# EC_meter_v2.net
KiCad netlist of a schematic drawn in Altium Designer
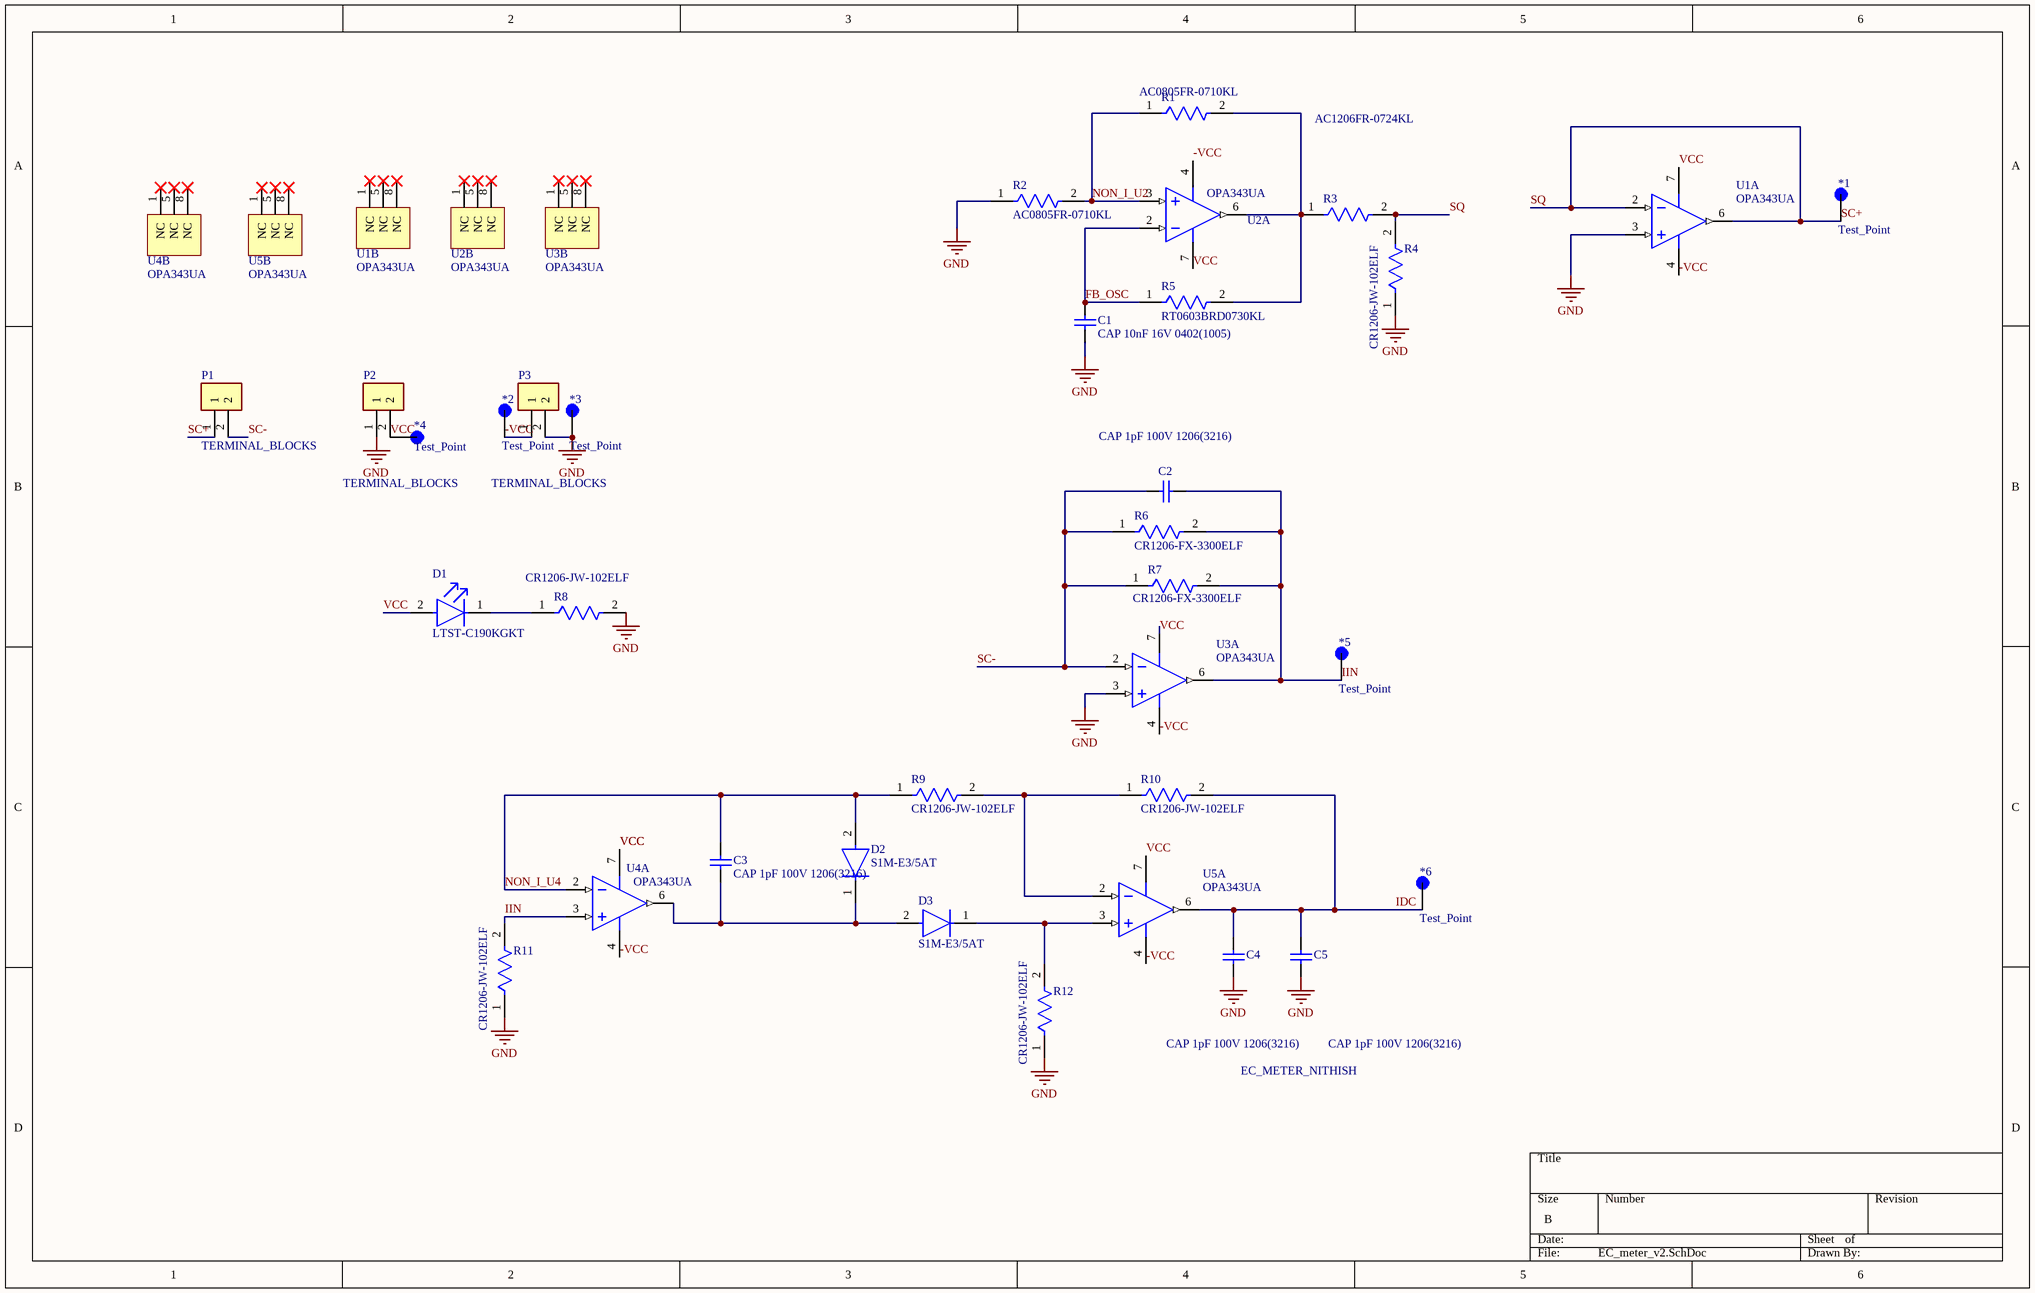
[diagram p0: EC_meter_v2.SchDoc]

(export (version "E")
  (design (tool "Eeschema 10.0.6"))
  (components
    (comp (ref "*1")
      (value "Test_Point")
      (footprint "Test_point")
      (libsource (lib "EC_meter_v2") (part "Test_Point"))
    )
    (comp (ref "*2")
      (value "Test_Point")
      (footprint "Test_point")
      (libsource (lib "EC_meter_v2") (part "Test_Point"))
    )
    (comp (ref "*3")
      (value "Test_Point")
      (footprint "Test_point")
      (libsource (lib "EC_meter_v2") (part "Test_Point"))
    )
    (comp (ref "*4")
      (value "Test_Point")
      (footprint "Test_point")
      (libsource (lib "EC_meter_v2") (part "Test_Point"))
    )
    (comp (ref "*5")
      (value "Test_Point")
      (footprint "Test_point")
      (libsource (lib "EC_meter_v2") (part "Test_Point"))
    )
    (comp (ref "*6")
      (value "Test_Point")
      (footprint "Test_point")
      (libsource (lib "EC_meter_v2") (part "Test_Point"))
    )
    (comp (ref "C1")
      (value "CAP 10nF 16V 0402(1005)")
      (footprint "CAPC0402(1005)60_M")
      (description "CAP 10nF 16V -20% to +80% 0402 (1005 Metric) Thickness 0.6mm SMD")
      (fields (field (name "TOLERANCE") "-20% to +80%"))
      (libsource (lib "Altium Content Vault") (part "CAP"))
    )
    (comp (ref "C2")
      (value "CAP 1pF 100V 1206(3216)")
      (footprint "CAPC1206(3216)170_N")
      (description "CAP 1pF 100V ±0.25pF 1206 (3216 Metric) Thickness 1.7mm SMD")
      (fields (field (name "TOLERANCE") "Â±0.25pF"))
      (libsource (lib "Altium Content Vault") (part "CAP"))
    )
    (comp (ref "C3")
      (value "CAP 1pF 100V 1206(3216)")
      (footprint "CAPC1206(3216)170_N")
      (description "CAP 1pF 100V ±0.25pF 1206 (3216 Metric) Thickness 1.7mm SMD")
      (fields (field (name "TOLERANCE") "Â±0.25pF"))
      (libsource (lib "Altium Content Vault") (part "CAP"))
    )
    (comp (ref "C4")
      (value "CAP 1pF 100V 1206(3216)")
      (footprint "CAPC1206(3216)170_N")
      (description "CAP 1pF 100V ±0.25pF 1206 (3216 Metric) Thickness 1.7mm SMD")
      (fields (field (name "TOLERANCE") "Â±0.25pF"))
      (libsource (lib "Altium Content Vault") (part "CAP"))
    )
    (comp (ref "C5")
      (value "CAP 1pF 100V 1206(3216)")
      (footprint "CAPC1206(3216)170_N")
      (description "CAP 1pF 100V ±0.25pF 1206 (3216 Metric) Thickness 1.7mm SMD")
      (fields (field (name "TOLERANCE") "Â±0.25pF"))
      (libsource (lib "Altium Content Vault") (part "CAP"))
    )
    (comp (ref "D1")
      (value "LTST-C190KGKT")
      (footprint "FP-LTST-C190KGKT-MFG")
      (description "LED GREEN CLEAR CHIP SMD")
      (libsource (lib "Altium Content Vault") (part "8706943c75ba83719d021d2fdc84c58"))
    )
    (comp (ref "D2")
      (value "S1M-E3/5AT")
      (footprint "FP-95400-MFG")
      (description "DIODE GEN PURP 1KV 1A DO214AC")
      (fields
        (field (name "OCTOPART") "https://octopart.com/s1m-e3%2F5at-vishay-42334588")
        (field (name "MANUFACTURER") "Vishay")
      )
      (libsource (lib "Altium Content Vault") (part "d7152d700b627762746794eb795d46e"))
    )
    (comp (ref "D3")
      (value "S1M-E3/5AT")
      (footprint "FP-95400-MFG")
      (description "DIODE GEN PURP 1KV 1A DO214AC")
      (fields
        (field (name "OCTOPART") "https://octopart.com/s1m-e3%2F5at-vishay-42334588")
        (field (name "MANUFACTURER") "Vishay")
      )
      (libsource (lib "Altium Content Vault") (part "d7152d700b627762746794eb795d46e"))
    )
    (comp (ref "P1")
      (value "TERMINAL_BLOCKS")
      (footprint "PCBComponent_1 - duplicate")
      (libsource (lib "EC_meter") (part "TERMINAL_BLOCKS"))
    )
    (comp (ref "P2")
      (value "TERMINAL_BLOCKS")
      (footprint "PCBComponent_1 - duplicate")
      (libsource (lib "EC_meter") (part "TERMINAL_BLOCKS"))
    )
    (comp (ref "P3")
      (value "TERMINAL_BLOCKS")
      (footprint "PCBComponent_1 - duplicate")
      (libsource (lib "EC_meter") (part "TERMINAL_BLOCKS"))
    )
    (comp (ref "R1")
      (value "AC0805FR-0710KL")
      (footprint "FP-AC0805-MFG")
      (description "RES SMD 10K OHM 1% 1/8W 0805")
      (fields
        (field (name "OCTOPART") "https://octopart.com/ac0805fr-0710kl-yageo-21711112")
        (field (name "MANUFACTURER") "Yageo")
      )
      (libsource (lib "Altium Content Vault") (part "1029c3af85768c4190bb7ad29bc67b5"))
    )
    (comp (ref "R2")
      (value "AC0805FR-0710KL")
      (footprint "FP-AC0805-MFG")
      (description "RES SMD 10K OHM 1% 1/8W 0805")
      (fields
        (field (name "OCTOPART") "https://octopart.com/ac0805fr-0710kl-yageo-21711112")
        (field (name "MANUFACTURER") "Yageo")
      )
      (libsource (lib "Altium Content Vault") (part "1029c3af85768c4190bb7ad29bc67b5"))
    )
    (comp (ref "R3")
      (value "AC1206FR-0724KL")
      (footprint "FP-AC1206-MFG")
      (description "RES SMD 24K OHM 1% 1/4W 1206")
      (fields
        (field (name "MANUFACTURER") "Yageo")
        (field (name "OCTOPART") "https://octopart.com/ac1206fr-0724kl-yageo-30511081")
      )
      (libsource (lib "Altium Content Vault") (part "1029c3af85768c4190bb7ad29bc67b5"))
    )
    (comp (ref "R4")
      (value "CR1206-JW-102ELF")
      (footprint "FP-CR1206-IPC_C")
      (description "Thick Film Chip Resistors 1206 1kΩ 0.25W 5% 200ppm/°C")
      (fields (field (name "TOLERANCE") "5%"))
      (libsource (lib "Altium Content Vault") (part "1029c3af85768c4190bb7ad29bc67b5"))
    )
    (comp (ref "R5")
      (value "RT0603BRD0730KL")
      (footprint "FP-RT0603-0_55-MFG")
      (fields (field (name "TOLERANCE") "0.1%"))
      (libsource (lib "Altium Content Vault") (part "1029c3af85768c4190bb7ad29bc67b5"))
    )
    (comp (ref "R6")
      (value "CR1206-FX-3300ELF")
      (footprint "FP-CR1206-MFG")
      (description "Thick Film Chip Resistors 1206 330Ω 0.25W 1% 100ppm/°C")
      (fields (field (name "TOLERANCE") "1%"))
      (libsource (lib "Altium Content Vault") (part "1029c3af85768c4190bb7ad29bc67b5"))
    )
    (comp (ref "R7")
      (value "CR1206-FX-3300ELF")
      (footprint "FP-CR1206-MFG")
      (description "Thick Film Chip Resistors 1206 330Ω 0.25W 1% 100ppm/°C")
      (fields (field (name "TOLERANCE") "1%"))
      (libsource (lib "Altium Content Vault") (part "1029c3af85768c4190bb7ad29bc67b5"))
    )
    (comp (ref "R8")
      (value "CR1206-JW-102ELF")
      (footprint "FP-CR1206-IPC_C")
      (description "Thick Film Chip Resistors 1206 1kΩ 0.25W 5% 200ppm/°C")
      (fields (field (name "TOLERANCE") "5%"))
      (libsource (lib "Altium Content Vault") (part "1029c3af85768c4190bb7ad29bc67b5"))
    )
    (comp (ref "R9")
      (value "CR1206-JW-102ELF")
      (footprint "FP-CR1206-IPC_C")
      (description "Thick Film Chip Resistors 1206 1kΩ 0.25W 5% 200ppm/°C")
      (fields (field (name "TOLERANCE") "5%"))
      (libsource (lib "Altium Content Vault") (part "1029c3af85768c4190bb7ad29bc67b5"))
    )
    (comp (ref "R10")
      (value "CR1206-JW-102ELF")
      (footprint "FP-CR1206-IPC_C")
      (description "Thick Film Chip Resistors 1206 1kΩ 0.25W 5% 200ppm/°C")
      (fields (field (name "TOLERANCE") "5%"))
      (libsource (lib "Altium Content Vault") (part "1029c3af85768c4190bb7ad29bc67b5"))
    )
    (comp (ref "R11")
      (value "CR1206-JW-102ELF")
      (footprint "FP-CR1206-IPC_C")
      (description "Thick Film Chip Resistors 1206 1kΩ 0.25W 5% 200ppm/°C")
      (fields (field (name "TOLERANCE") "5%"))
      (libsource (lib "Altium Content Vault") (part "1029c3af85768c4190bb7ad29bc67b5"))
    )
    (comp (ref "R12")
      (value "CR1206-JW-102ELF")
      (footprint "FP-CR1206-IPC_C")
      (description "Thick Film Chip Resistors 1206 1kΩ 0.25W 5% 200ppm/°C")
      (fields (field (name "TOLERANCE") "5%"))
      (libsource (lib "Altium Content Vault") (part "1029c3af85768c4190bb7ad29bc67b5"))
    )
    (comp (ref "U1")
      (value "OPA343UA")
      (footprint "D0008A_M")
      (fields (field (name "MANUFACTURER") "Texas Instruments"))
      (libsource (lib "Altium Content Vault") (part "TI-OPA-8_1"))
    )
    (comp (ref "U2")
      (value "OPA343UA")
      (footprint "D0008A_M")
      (fields (field (name "MANUFACTURER") "Texas Instruments"))
      (libsource (lib "Altium Content Vault") (part "TI-OPA-8_1"))
    )
    (comp (ref "U3")
      (value "OPA343UA")
      (footprint "D0008A_M")
      (fields (field (name "MANUFACTURER") "Texas Instruments"))
      (libsource (lib "") (part "TI-OPA-8_1_1"))
    )
    (comp (ref "U4")
      (value "OPA343UA")
      (footprint "D0008A_M")
      (fields (field (name "MANUFACTURER") "Texas Instruments"))
      (libsource (lib "") (part "TI-OPA-8_1_1"))
    )
    (comp (ref "U5")
      (value "OPA343UA")
      (footprint "D0008A_M")
      (fields (field (name "MANUFACTURER") "Texas Instruments"))
      (libsource (lib "") (part "TI-OPA-8_1_1"))
    )
  )
  (nets
    (net (code "1") (name "/-VCC") (class "Default")
      (node (ref "*2") (pin "1") (pinfunction "TP_1") (pintype "passive"))
      (node (ref "P3") (pin "1") (pinfunction "1_1") (pintype "passive"))
      (node (ref "U1") (pin "4") (pinfunction "V-_4") (pintype "power_in"))
      (node (ref "U2") (pin "4") (pinfunction "V-_4") (pintype "power_in"))
      (node (ref "U3") (pin "4") (pinfunction "V-_4") (pintype "power_in"))
      (node (ref "U4") (pin "4") (pinfunction "V-_4") (pintype "power_in"))
      (node (ref "U5") (pin "4") (pinfunction "V-_4") (pintype "power_in"))
    )
    (net (code "2") (name "/FB_OSC") (class "Default")
      (node (ref "C1") (pin "2") (pinfunction "2_2") (pintype "passive"))
      (node (ref "R5") (pin "1") (pinfunction "1_1") (pintype "passive"))
      (node (ref "U2") (pin "2") (pinfunction "IN-_2") (pintype "input"))
    )
    (net (code "3") (name "/IDC") (class "Default")
      (node (ref "*6") (pin "1") (pinfunction "TP_1") (pintype "passive"))
      (node (ref "C4") (pin "2") (pinfunction "2_2") (pintype "passive"))
      (node (ref "C5") (pin "2") (pinfunction "2_2") (pintype "passive"))
      (node (ref "R10") (pin "2") (pinfunction "2_2") (pintype "passive"))
      (node (ref "U5") (pin "6") (pinfunction "OUT_6") (pintype "output"))
    )
    (net (code "4") (name "/IIN") (class "Default")
      (node (ref "*5") (pin "1") (pinfunction "TP_1") (pintype "passive"))
      (node (ref "C2") (pin "1") (pinfunction "1_1") (pintype "passive"))
      (node (ref "R11") (pin "2") (pinfunction "2_2") (pintype "passive"))
      (node (ref "R6") (pin "2") (pinfunction "2_2") (pintype "passive"))
      (node (ref "R7") (pin "2") (pinfunction "2_2") (pintype "passive"))
      (node (ref "U3") (pin "6") (pinfunction "OUT_6") (pintype "output"))
      (node (ref "U4") (pin "3") (pinfunction "IN+_3") (pintype "input"))
    )
    (net (code "5") (name "/NON_I_U2") (class "Default")
      (node (ref "R1") (pin "1") (pinfunction "1_1") (pintype "passive"))
      (node (ref "R2") (pin "2") (pinfunction "2_2") (pintype "passive"))
      (node (ref "U2") (pin "3") (pinfunction "IN+_3") (pintype "input"))
    )
    (net (code "6") (name "/NON_I_U4") (class "Default")
      (node (ref "C3") (pin "2") (pinfunction "2_2") (pintype "passive"))
      (node (ref "D2") (pin "2") (pinfunction "A_2") (pintype "passive"))
      (node (ref "R9") (pin "1") (pinfunction "1_1") (pintype "passive"))
      (node (ref "U4") (pin "2") (pinfunction "IN-_2") (pintype "input"))
    )
    (net (code "7") (name "/SC+") (class "Default")
      (node (ref "*1") (pin "1") (pinfunction "TP_1") (pintype "passive"))
      (node (ref "P1") (pin "1") (pinfunction "1_1") (pintype "passive"))
      (node (ref "R3") (pin "2") (pinfunction "2_2") (pintype "passive"))
      (node (ref "R4") (pin "2") (pinfunction "2_2") (pintype "passive"))
      (node (ref "U1") (pin "2") (pinfunction "IN-_2") (pintype "input"))
      (node (ref "U1") (pin "6") (pinfunction "OUT_6") (pintype "output"))
    )
    (net (code "8") (name "/SC-") (class "Default")
      (node (ref "C2") (pin "2") (pinfunction "2_2") (pintype "passive"))
      (node (ref "P1") (pin "2") (pinfunction "2_2") (pintype "passive"))
      (node (ref "R6") (pin "1") (pinfunction "1_1") (pintype "passive"))
      (node (ref "R7") (pin "1") (pinfunction "1_1") (pintype "passive"))
      (node (ref "U3") (pin "2") (pinfunction "IN-_2") (pintype "input"))
    )
    (net (code "9") (name "/VCC") (class "Default")
      (node (ref "*4") (pin "1") (pinfunction "TP_1") (pintype "passive"))
      (node (ref "D1") (pin "2") (pinfunction "A_2") (pintype "passive"))
      (node (ref "P2") (pin "2") (pinfunction "2_2") (pintype "passive"))
      (node (ref "U1") (pin "7") (pinfunction "V+_7") (pintype "power_in"))
      (node (ref "U2") (pin "7") (pinfunction "V+_7") (pintype "power_in"))
      (node (ref "U3") (pin "7") (pinfunction "V+_7") (pintype "power_in"))
      (node (ref "U4") (pin "7") (pinfunction "V+_7") (pintype "power_in"))
      (node (ref "U5") (pin "7") (pinfunction "V+_7") (pintype "power_in"))
    )
    (net (code "10") (name "GND") (class "Default")
      (node (ref "*3") (pin "1") (pinfunction "TP_1") (pintype "passive"))
      (node (ref "C1") (pin "1") (pinfunction "1_1") (pintype "passive"))
      (node (ref "C4") (pin "1") (pinfunction "1_1") (pintype "passive"))
      (node (ref "C5") (pin "1") (pinfunction "1_1") (pintype "passive"))
      (node (ref "P2") (pin "1") (pinfunction "1_1") (pintype "passive"))
      (node (ref "P3") (pin "2") (pinfunction "2_2") (pintype "passive"))
      (node (ref "R11") (pin "1") (pinfunction "1_1") (pintype "passive"))
      (node (ref "R12") (pin "1") (pinfunction "1_1") (pintype "passive"))
      (node (ref "R2") (pin "1") (pinfunction "1_1") (pintype "passive"))
      (node (ref "R4") (pin "1") (pinfunction "1_1") (pintype "passive"))
      (node (ref "R8") (pin "2") (pinfunction "2_2") (pintype "passive"))
      (node (ref "U1") (pin "3") (pinfunction "IN+_3") (pintype "input"))
      (node (ref "U3") (pin "3") (pinfunction "IN+_3") (pintype "input"))
    )
    (net (code "11") (name "Net-(D1-C)") (class "Default")
      (node (ref "D1") (pin "1") (pinfunction "C_1") (pintype "passive"))
      (node (ref "R8") (pin "1") (pinfunction "1_1") (pintype "passive"))
    )
    (net (code "12") (name "Net-(D2-C)") (class "Default")
      (node (ref "C3") (pin "1") (pinfunction "1_1") (pintype "passive"))
      (node (ref "D2") (pin "1") (pinfunction "C_1") (pintype "passive"))
      (node (ref "D3") (pin "2") (pinfunction "A_2") (pintype "passive"))
      (node (ref "U4") (pin "6") (pinfunction "OUT_6") (pintype "output"))
    )
    (net (code "13") (name "Net-(D3-C)") (class "Default")
      (node (ref "D3") (pin "1") (pinfunction "C_1") (pintype "passive"))
      (node (ref "R12") (pin "2") (pinfunction "2_2") (pintype "passive"))
      (node (ref "U5") (pin "3") (pinfunction "IN+_3") (pintype "input"))
    )
    (net (code "14") (name "Net-(U2A-OUT)") (class "Default")
      (node (ref "R1") (pin "2") (pinfunction "2_2") (pintype "passive"))
      (node (ref "R3") (pin "1") (pinfunction "1_1") (pintype "passive"))
      (node (ref "R5") (pin "2") (pinfunction "2_2") (pintype "passive"))
      (node (ref "U2") (pin "6") (pinfunction "OUT_6") (pintype "output"))
    )
    (net (code "15") (name "Net-(U5A-IN-)") (class "Default")
      (node (ref "R10") (pin "1") (pinfunction "1_1") (pintype "passive"))
      (node (ref "R9") (pin "2") (pinfunction "2_2") (pintype "passive"))
      (node (ref "U5") (pin "2") (pinfunction "IN-_2") (pintype "input"))
    )
    (net (code "16") (name "unconnected-(U1B-NC-Pad1)") (class "Default")
      (node (ref "U1") (pin "1") (pinfunction "NC_1") (pintype "passive+no_connect"))
    )
    (net (code "17") (name "unconnected-(U1B-NC-Pad5)") (class "Default")
      (node (ref "U1") (pin "5") (pinfunction "NC_5") (pintype "passive+no_connect"))
    )
    (net (code "18") (name "unconnected-(U1B-NC-Pad8)") (class "Default")
      (node (ref "U1") (pin "8") (pinfunction "NC_8") (pintype "passive+no_connect"))
    )
    (net (code "19") (name "unconnected-(U2B-NC-Pad1)") (class "Default")
      (node (ref "U2") (pin "1") (pinfunction "NC_1") (pintype "passive+no_connect"))
    )
    (net (code "20") (name "unconnected-(U2B-NC-Pad5)") (class "Default")
      (node (ref "U2") (pin "5") (pinfunction "NC_5") (pintype "passive+no_connect"))
    )
    (net (code "21") (name "unconnected-(U2B-NC-Pad8)") (class "Default")
      (node (ref "U2") (pin "8") (pinfunction "NC_8") (pintype "passive+no_connect"))
    )
    (net (code "22") (name "unconnected-(U3B-NC-Pad1)") (class "Default")
      (node (ref "U3") (pin "1") (pinfunction "NC_1") (pintype "passive+no_connect"))
    )
    (net (code "23") (name "unconnected-(U3B-NC-Pad5)") (class "Default")
      (node (ref "U3") (pin "5") (pinfunction "NC_5") (pintype "passive+no_connect"))
    )
    (net (code "24") (name "unconnected-(U3B-NC-Pad8)") (class "Default")
      (node (ref "U3") (pin "8") (pinfunction "NC_8") (pintype "passive+no_connect"))
    )
    (net (code "25") (name "unconnected-(U4B-NC-Pad1)") (class "Default")
      (node (ref "U4") (pin "1") (pinfunction "NC_1") (pintype "passive+no_connect"))
    )
    (net (code "26") (name "unconnected-(U4B-NC-Pad5)") (class "Default")
      (node (ref "U4") (pin "5") (pinfunction "NC_5") (pintype "passive+no_connect"))
    )
    (net (code "27") (name "unconnected-(U4B-NC-Pad8)") (class "Default")
      (node (ref "U4") (pin "8") (pinfunction "NC_8") (pintype "passive+no_connect"))
    )
    (net (code "28") (name "unconnected-(U5B-NC-Pad1)") (class "Default")
      (node (ref "U5") (pin "1") (pinfunction "NC_1") (pintype "passive+no_connect"))
    )
    (net (code "29") (name "unconnected-(U5B-NC-Pad5)") (class "Default")
      (node (ref "U5") (pin "5") (pinfunction "NC_5") (pintype "passive+no_connect"))
    )
    (net (code "30") (name "unconnected-(U5B-NC-Pad8)") (class "Default")
      (node (ref "U5") (pin "8") (pinfunction "NC_8") (pintype "passive+no_connect"))
    )
  )
)
